# rev2.net
KiCad netlist of a schematic drawn in EAGLE
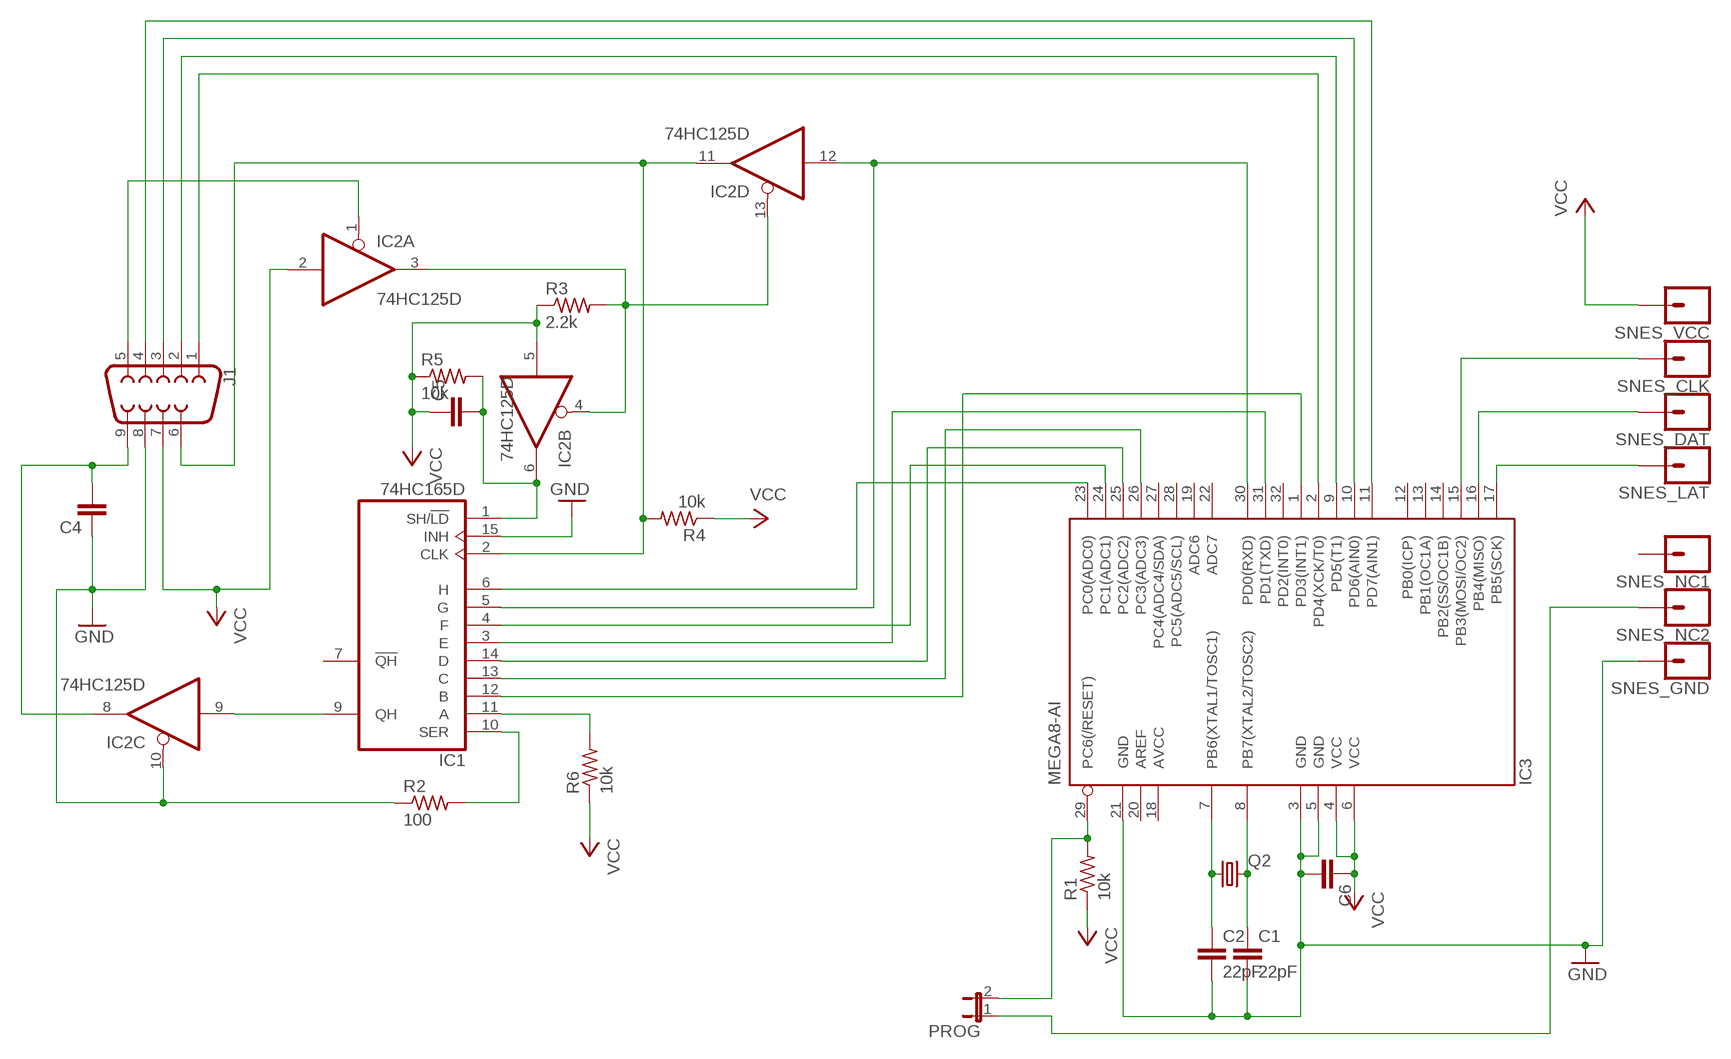
[diagram p0: schematic, sheet 1]

(export (version "E")
  (design (tool "Eeschema 10.0.6"))
  (components
    (comp (ref "C1")
      (value "22pF")
      (footprint "eagle-import:C1206")
      (libsource (lib "eagle-import") (part "C-EUC1206"))
    )
    (comp (ref "C2")
      (value "22pF")
      (footprint "eagle-import:C1206")
      (libsource (lib "eagle-import") (part "C-EUC1206"))
    )
    (comp (ref "C4")
      (value "C-EUC1206")
      (footprint "eagle-import:C1206")
      (libsource (lib "eagle-import") (part "C-EUC1206"))
    )
    (comp (ref "C5")
      (value "C-EUC1206")
      (footprint "eagle-import:C1206")
      (libsource (lib "eagle-import") (part "C-EUC1206"))
    )
    (comp (ref "C6")
      (value "C-EUC1206")
      (footprint "eagle-import:C1206")
      (libsource (lib "eagle-import") (part "C-EUC1206"))
    )
    (comp (ref "IC1")
      (value "74HC165D")
      (footprint "eagle-import:SO16")
      (libsource (lib "eagle-import") (part "74165DHC"))
    )
    (comp (ref "IC2")
      (value "74HC125D")
      (footprint "eagle-import:SO14")
      (libsource (lib "eagle-import") (part "74125DHC"))
    )
    (comp (ref "IC3")
      (value "MEGA8-AI")
      (footprint "eagle-import:TQFP32-08")
      (fields (field (name "MPN") "ATMEGA8-16AU"))
      (libsource (lib "eagle-import") (part "MEGA8-AI"))
    )
    (comp (ref "J1")
      (value "DB9FEMALE")
      (footprint "eagle-import:DB9")
      (libsource (lib "eagle-import") (part "DB9FEMALE"))
    )
    (comp (ref "PROG")
      (value "JP1E")
      (footprint "eagle-import:JP1")
      (libsource (lib "eagle-import") (part "JP1E"))
    )
    (comp (ref "Q2")
      (value "CRYSTALHC49S")
      (footprint "eagle-import:HC49_S")
      (libsource (lib "eagle-import") (part "CRYSTALHC49S"))
    )
    (comp (ref "R1")
      (value "10k")
      (footprint "eagle-import:R1206")
      (libsource (lib "eagle-import") (part "R-US_R1206"))
    )
    (comp (ref "R2")
      (value "100")
      (footprint "eagle-import:R1206")
      (libsource (lib "eagle-import") (part "R-US_R1206"))
    )
    (comp (ref "R3")
      (value "2.2k")
      (footprint "eagle-import:R1206")
      (libsource (lib "eagle-import") (part "R-US_R1206"))
    )
    (comp (ref "R4")
      (value "10k")
      (footprint "eagle-import:R1206")
      (libsource (lib "eagle-import") (part "R-US_R1206"))
    )
    (comp (ref "R5")
      (value "10k")
      (footprint "eagle-import:R1206")
      (libsource (lib "eagle-import") (part "R-US_R1206"))
    )
    (comp (ref "R6")
      (value "10k")
      (footprint "eagle-import:R1206")
      (libsource (lib "eagle-import") (part "R-US_R1206"))
    )
    (comp (ref "SNES_CLK")
      (value "CONN_01PTH_2MM")
      (footprint "eagle-import:1X01_2MM")
      (libsource (lib "eagle-import") (part "CONN_01PTH_2MM"))
    )
    (comp (ref "SNES_DAT")
      (value "CONN_01PTH_2MM")
      (footprint "eagle-import:1X01_2MM")
      (libsource (lib "eagle-import") (part "CONN_01PTH_2MM"))
    )
    (comp (ref "SNES_GND")
      (value "CONN_01PTH_2MM")
      (footprint "eagle-import:1X01_2MM")
      (libsource (lib "eagle-import") (part "CONN_01PTH_2MM"))
    )
    (comp (ref "SNES_LAT")
      (value "CONN_01PTH_2MM")
      (footprint "eagle-import:1X01_2MM")
      (libsource (lib "eagle-import") (part "CONN_01PTH_2MM"))
    )
    (comp (ref "SNES_NC1")
      (value "CONN_01PTH_2MM")
      (footprint "eagle-import:1X01_2MM")
      (libsource (lib "eagle-import") (part "CONN_01PTH_2MM"))
    )
    (comp (ref "SNES_NC2")
      (value "CONN_01PTH_2MM")
      (footprint "eagle-import:1X01_2MM")
      (libsource (lib "eagle-import") (part "CONN_01PTH_2MM"))
    )
    (comp (ref "SNES_VCC")
      (value "CONN_01PTH_2MM")
      (footprint "eagle-import:1X01_2MM")
      (libsource (lib "eagle-import") (part "CONN_01PTH_2MM"))
    )
  )
  (nets
    (net (code "1") (name "/AVCC") (class "Default")
      (node (ref "IC3") (pin "18") (pinfunction "AVCC_18") (pintype "power_in"))
    )
    (net (code "2") (name "GND") (class "Default")
      (node (ref "C1") (pin "2") (pinfunction "2_2") (pintype "passive"))
      (node (ref "C2") (pin "2") (pinfunction "2_2") (pintype "passive"))
      (node (ref "C4") (pin "1") (pinfunction "1_1") (pintype "passive"))
      (node (ref "C6") (pin "2") (pinfunction "2_2") (pintype "passive"))
      (node (ref "IC1") (pin "15") (pinfunction "INH_15") (pintype "input"))
      (node (ref "IC2") (pin "10") (pinfunction "OE_10") (pintype "input"))
      (node (ref "IC3") (pin "21") (pinfunction "GND_21") (pintype "power_in"))
      (node (ref "IC3") (pin "3") (pinfunction "GND_3") (pintype "power_in"))
      (node (ref "IC3") (pin "5") (pinfunction "GND_5") (pintype "power_in"))
      (node (ref "J1") (pin "8") (pinfunction "8_8") (pintype "passive"))
      (node (ref "R2") (pin "1") (pinfunction "1_1") (pintype "passive"))
      (node (ref "SNES_GND") (pin "1") (pinfunction "1_1") (pintype "passive"))
    )
    (net (code "3") (name "Net-(IC1A-A)") (class "Default")
      (node (ref "IC1") (pin "11") (pinfunction "A_11") (pintype "input"))
      (node (ref "R6") (pin "2") (pinfunction "2_2") (pintype "passive"))
    )
    (net (code "4") (name "Net-(IC1A-B)") (class "Default")
      (node (ref "IC1") (pin "12") (pinfunction "B_12") (pintype "input"))
      (node (ref "IC3") (pin "1") (pinfunction "PD3(INT1)_1") (pintype "bidirectional"))
    )
    (net (code "5") (name "Net-(IC1A-C)") (class "Default")
      (node (ref "IC1") (pin "13") (pinfunction "C_13") (pintype "input"))
      (node (ref "IC3") (pin "26") (pinfunction "PC3(ADC3)_26") (pintype "bidirectional"))
    )
    (net (code "6") (name "Net-(IC1A-CLK)") (class "Default")
      (node (ref "IC1") (pin "2") (pinfunction "CLK_2") (pintype "input"))
      (node (ref "IC2") (pin "11") (pinfunction "O_11") (pintype "tri_state"))
      (node (ref "J1") (pin "6") (pinfunction "6_6") (pintype "passive"))
      (node (ref "R4") (pin "2") (pinfunction "2_2") (pintype "passive"))
    )
    (net (code "7") (name "Net-(IC1A-D)") (class "Default")
      (node (ref "IC1") (pin "14") (pinfunction "D_14") (pintype "input"))
      (node (ref "IC3") (pin "25") (pinfunction "PC2(ADC2)_25") (pintype "bidirectional"))
    )
    (net (code "8") (name "Net-(IC1A-E)") (class "Default")
      (node (ref "IC1") (pin "3") (pinfunction "E_3") (pintype "input"))
      (node (ref "IC3") (pin "31") (pinfunction "PD1(TXD)_31") (pintype "bidirectional"))
    )
    (net (code "9") (name "Net-(IC1A-F)") (class "Default")
      (node (ref "IC1") (pin "4") (pinfunction "F_4") (pintype "input"))
      (node (ref "IC3") (pin "24") (pinfunction "PC1(ADC1)_24") (pintype "bidirectional"))
    )
    (net (code "10") (name "Net-(IC1A-G)") (class "Default")
      (node (ref "IC1") (pin "5") (pinfunction "G_5") (pintype "input"))
      (node (ref "IC2") (pin "12") (pinfunction "I_12") (pintype "input"))
      (node (ref "IC3") (pin "30") (pinfunction "PD0(RXD)_30") (pintype "bidirectional"))
    )
    (net (code "11") (name "Net-(IC1A-H)") (class "Default")
      (node (ref "IC1") (pin "6") (pinfunction "H_6") (pintype "input"))
      (node (ref "IC3") (pin "23") (pinfunction "PC0(ADC0)_23") (pintype "bidirectional"))
    )
    (net (code "12") (name "Net-(IC1A-QH)") (class "Default")
      (node (ref "IC1") (pin "9") (pinfunction "QH_9") (pintype "output"))
      (node (ref "IC2") (pin "9") (pinfunction "I_9") (pintype "input"))
    )
    (net (code "13") (name "Net-(IC1A-SER)") (class "Default")
      (node (ref "IC1") (pin "10") (pinfunction "SER_10") (pintype "input"))
      (node (ref "R2") (pin "2") (pinfunction "2_2") (pintype "passive"))
    )
    (net (code "14") (name "Net-(IC1A-SH{slash}~{LD})") (class "Default")
      (node (ref "C5") (pin "2") (pinfunction "2_2") (pintype "passive"))
      (node (ref "IC1") (pin "1") (pinfunction "SH/~{LD}_1") (pintype "input"))
      (node (ref "IC2") (pin "6") (pinfunction "O_6") (pintype "tri_state"))
      (node (ref "R5") (pin "2") (pinfunction "2_2") (pintype "passive"))
    )
    (net (code "15") (name "Net-(IC2A-O)") (class "Default")
      (node (ref "IC2") (pin "13") (pinfunction "OE_13") (pintype "input"))
      (node (ref "IC2") (pin "3") (pinfunction "O_3") (pintype "tri_state"))
      (node (ref "IC2") (pin "4") (pinfunction "OE_4") (pintype "input"))
      (node (ref "R3") (pin "2") (pinfunction "2_2") (pintype "passive"))
    )
    (net (code "16") (name "Net-(IC2A-OE)") (class "Default")
      (node (ref "IC2") (pin "1") (pinfunction "OE_1") (pintype "input"))
      (node (ref "J1") (pin "5") (pinfunction "5_5") (pintype "passive"))
    )
    (net (code "17") (name "Net-(IC2C-O)") (class "Default")
      (node (ref "C4") (pin "2") (pinfunction "2_2") (pintype "passive"))
      (node (ref "IC2") (pin "8") (pinfunction "O_8") (pintype "tri_state"))
      (node (ref "J1") (pin "9") (pinfunction "9_9") (pintype "passive"))
    )
    (net (code "18") (name "Net-(IC3-PB3(MOSI{slash}OC2))") (class "Default")
      (node (ref "IC3") (pin "15") (pinfunction "PB3(MOSI/OC2)_15") (pintype "bidirectional"))
      (node (ref "SNES_CLK") (pin "1") (pinfunction "1_1") (pintype "passive"))
    )
    (net (code "19") (name "Net-(IC3-PB4(MISO))") (class "Default")
      (node (ref "IC3") (pin "16") (pinfunction "PB4(MISO)_16") (pintype "bidirectional"))
      (node (ref "SNES_DAT") (pin "1") (pinfunction "1_1") (pintype "passive"))
    )
    (net (code "20") (name "Net-(IC3-PB5(SCK))") (class "Default")
      (node (ref "IC3") (pin "17") (pinfunction "PB5(SCK)_17") (pintype "bidirectional"))
      (node (ref "SNES_LAT") (pin "1") (pinfunction "1_1") (pintype "passive"))
    )
    (net (code "21") (name "Net-(IC3-PB6(XTAL1{slash}TOSC1))") (class "Default")
      (node (ref "C2") (pin "1") (pinfunction "1_1") (pintype "passive"))
      (node (ref "IC3") (pin "7") (pinfunction "PB6(XTAL1/TOSC1)_7") (pintype "bidirectional"))
      (node (ref "Q2") (pin "1") (pinfunction "1_1") (pintype "passive"))
    )
    (net (code "22") (name "Net-(IC3-PB7(XTAL2{slash}TOSC2))") (class "Default")
      (node (ref "C1") (pin "1") (pinfunction "1_1") (pintype "passive"))
      (node (ref "IC3") (pin "8") (pinfunction "PB7(XTAL2/TOSC2)_8") (pintype "bidirectional"))
      (node (ref "Q2") (pin "2") (pinfunction "2_2") (pintype "passive"))
    )
    (net (code "23") (name "Net-(IC3-PC6({slash}RESET))") (class "Default")
      (node (ref "IC3") (pin "29") (pinfunction "PC6(/RESET)_29") (pintype "bidirectional"))
      (node (ref "PROG") (pin "2") (pinfunction "2_2") (pintype "passive"))
      (node (ref "R1") (pin "2") (pinfunction "2_2") (pintype "passive"))
    )
    (net (code "24") (name "Net-(IC3-PD4(XCK{slash}T0))") (class "Default")
      (node (ref "IC3") (pin "2") (pinfunction "PD4(XCK/T0)_2") (pintype "bidirectional"))
      (node (ref "J1") (pin "1") (pinfunction "1_1") (pintype "passive"))
    )
    (net (code "25") (name "Net-(IC3-PD5(T1))") (class "Default")
      (node (ref "IC3") (pin "9") (pinfunction "PD5(T1)_9") (pintype "bidirectional"))
      (node (ref "J1") (pin "2") (pinfunction "2_2") (pintype "passive"))
    )
    (net (code "26") (name "Net-(IC3-PD6(AIN0))") (class "Default")
      (node (ref "IC3") (pin "10") (pinfunction "PD6(AIN0)_10") (pintype "bidirectional"))
      (node (ref "J1") (pin "3") (pinfunction "3_3") (pintype "passive"))
    )
    (net (code "27") (name "Net-(IC3-PD7(AIN1))") (class "Default")
      (node (ref "IC3") (pin "11") (pinfunction "PD7(AIN1)_11") (pintype "bidirectional"))
      (node (ref "J1") (pin "4") (pinfunction "4_4") (pintype "passive"))
    )
    (net (code "28") (name "Net-(PROG-Pad1)") (class "Default")
      (node (ref "PROG") (pin "1") (pinfunction "1_1") (pintype "passive"))
      (node (ref "SNES_NC2") (pin "1") (pinfunction "1_1") (pintype "passive"))
    )
    (net (code "29") (name "VCC") (class "Default")
      (node (ref "C5") (pin "1") (pinfunction "1_1") (pintype "passive"))
      (node (ref "C6") (pin "1") (pinfunction "1_1") (pintype "passive"))
      (node (ref "IC2") (pin "2") (pinfunction "I_2") (pintype "input"))
      (node (ref "IC2") (pin "5") (pinfunction "I_5") (pintype "input"))
      (node (ref "IC3") (pin "4") (pinfunction "VCC_4") (pintype "power_in"))
      (node (ref "IC3") (pin "6") (pinfunction "VCC_6") (pintype "power_in"))
      (node (ref "J1") (pin "7") (pinfunction "7_7") (pintype "passive"))
      (node (ref "R1") (pin "1") (pinfunction "1_1") (pintype "passive"))
      (node (ref "R3") (pin "1") (pinfunction "1_1") (pintype "passive"))
      (node (ref "R4") (pin "1") (pinfunction "1_1") (pintype "passive"))
      (node (ref "R5") (pin "1") (pinfunction "1_1") (pintype "passive"))
      (node (ref "R6") (pin "1") (pinfunction "1_1") (pintype "passive"))
      (node (ref "SNES_VCC") (pin "1") (pinfunction "1_1") (pintype "passive"))
    )
    (net (code "30") (name "unconnected-(IC1A-~{QH}-Pad7)") (class "Default")
      (node (ref "IC1") (pin "7") (pinfunction "~{QH}_7") (pintype "output"))
    )
    (net (code "31") (name "unconnected-(IC3-ADC6-Pad19)") (class "Default")
      (node (ref "IC3") (pin "19") (pinfunction "ADC6_19") (pintype "bidirectional"))
    )
    (net (code "32") (name "unconnected-(IC3-ADC7-Pad22)") (class "Default")
      (node (ref "IC3") (pin "22") (pinfunction "ADC7_22") (pintype "bidirectional"))
    )
    (net (code "33") (name "unconnected-(IC3-AREF-Pad20)") (class "Default")
      (node (ref "IC3") (pin "20") (pinfunction "AREF_20") (pintype "passive"))
    )
    (net (code "34") (name "unconnected-(IC3-PB0(ICP)-Pad12)") (class "Default")
      (node (ref "IC3") (pin "12") (pinfunction "PB0(ICP)_12") (pintype "bidirectional"))
    )
    (net (code "35") (name "unconnected-(IC3-PB1(OC1A)-Pad13)") (class "Default")
      (node (ref "IC3") (pin "13") (pinfunction "PB1(OC1A)_13") (pintype "bidirectional"))
    )
    (net (code "36") (name "unconnected-(IC3-PB2(SS{slash}OC1B)-Pad14)") (class "Default")
      (node (ref "IC3") (pin "14") (pinfunction "PB2(SS/OC1B)_14") (pintype "bidirectional"))
    )
    (net (code "37") (name "unconnected-(IC3-PC4(ADC4{slash}SDA)-Pad27)") (class "Default")
      (node (ref "IC3") (pin "27") (pinfunction "PC4(ADC4/SDA)_27") (pintype "bidirectional"))
    )
    (net (code "38") (name "unconnected-(IC3-PC5(ADC5{slash}SCL)-Pad28)") (class "Default")
      (node (ref "IC3") (pin "28") (pinfunction "PC5(ADC5/SCL)_28") (pintype "bidirectional"))
    )
    (net (code "39") (name "unconnected-(IC3-PD2(INT0)-Pad32)") (class "Default")
      (node (ref "IC3") (pin "32") (pinfunction "PD2(INT0)_32") (pintype "bidirectional"))
    )
    (net (code "40") (name "unconnected-(SNES_NC1-Pad1)") (class "Default")
      (node (ref "SNES_NC1") (pin "1") (pinfunction "1_1") (pintype "passive"))
    )
  )
)
